# sdcard_ram.net
KiCad netlist of a schematic drawn in Altium Designer
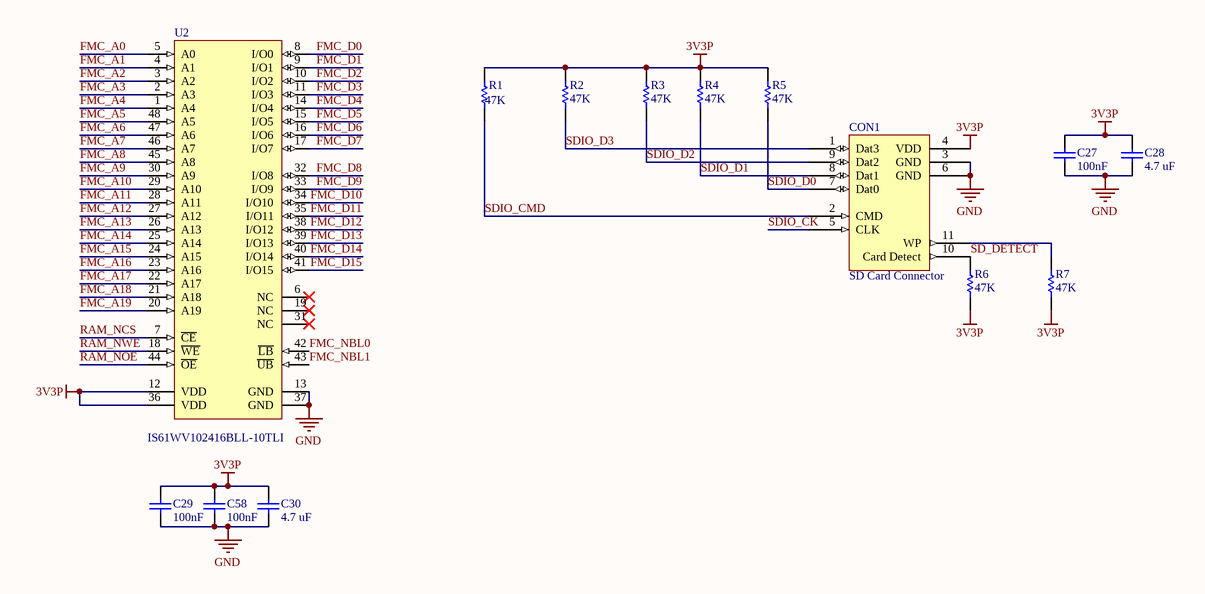
[diagram p0: sdcard_ram.SchDoc]

(export (version "E")
  (design (tool "Eeschema 10.0.6"))
  (components
    (comp (ref "C27")
      (value "100nF")
      (footprint "C0805")
      (description "Capacitor")
      (fields (field (name "PUBLISHER") "Altium Limited"))
      (libsource (lib "Miscellaneous Devices") (part "Cap"))
    )
    (comp (ref "C28")
      (value "4.7 uF")
      (footprint "C0805")
      (description "Capacitor")
      (fields (field (name "PUBLISHER") "Altium Limited"))
      (libsource (lib "Miscellaneous Devices") (part "Cap"))
    )
    (comp (ref "C29")
      (value "100nF")
      (footprint "C0805")
      (description "Capacitor")
      (fields (field (name "PUBLISHER") "Altium Limited"))
      (libsource (lib "Miscellaneous Devices") (part "Cap"))
    )
    (comp (ref "C30")
      (value "4.7 uF")
      (footprint "C0805")
      (description "Capacitor")
      (fields (field (name "PUBLISHER") "Altium Limited"))
      (libsource (lib "Miscellaneous Devices") (part "Cap"))
    )
    (comp (ref "C58")
      (value "100nF")
      (footprint "C0805")
      (description "Capacitor")
      (fields (field (name "PUBLISHER") "Altium Limited"))
      (libsource (lib "Miscellaneous Devices") (part "Cap"))
    )
    (comp (ref "CON1")
      (value "SD Card Connector")
      (footprint "SD_card_fp")
      (description "3M™ Card Connector SD™")
      (libsource (lib "GameMan") (part "SD Card Connector"))
    )
    (comp (ref "R1")
      (value "47K")
      (footprint "6-0805_M")
      (description "Resistor")
      (fields (field (name "PUBLISHER") "Altium Limited"))
      (libsource (lib "Miscellaneous Devices") (part "Res1"))
    )
    (comp (ref "R2")
      (value "47K")
      (footprint "6-0805_M")
      (description "Resistor")
      (fields (field (name "PUBLISHER") "Altium Limited"))
      (libsource (lib "Miscellaneous Devices") (part "Res1"))
    )
    (comp (ref "R3")
      (value "47K")
      (footprint "6-0805_M")
      (description "Resistor")
      (fields (field (name "PUBLISHER") "Altium Limited"))
      (libsource (lib "Miscellaneous Devices") (part "Res1"))
    )
    (comp (ref "R4")
      (value "47K")
      (footprint "6-0805_M")
      (description "Resistor")
      (fields (field (name "PUBLISHER") "Altium Limited"))
      (libsource (lib "Miscellaneous Devices") (part "Res1"))
    )
    (comp (ref "R5")
      (value "47K")
      (footprint "6-0805_M")
      (description "Resistor")
      (fields (field (name "PUBLISHER") "Altium Limited"))
      (libsource (lib "Miscellaneous Devices") (part "Res1"))
    )
    (comp (ref "R6")
      (value "47K")
      (footprint "6-0805_M")
      (description "Resistor")
      (fields (field (name "PUBLISHER") "Altium Limited"))
      (libsource (lib "Miscellaneous Devices") (part "Res1"))
    )
    (comp (ref "R7")
      (value "47K")
      (footprint "6-0805_M")
      (description "Resistor")
      (fields (field (name "PUBLISHER") "Altium Limited"))
      (libsource (lib "Miscellaneous Devices") (part "Res1"))
    )
    (comp (ref "U2")
      (value "IS61WV102416BLL-10TLI")
      (footprint "ISSI-TSOP-1-48-12000X20000DE_N")
      (fields (field (name "MANUFACTURER") "Integrated Silicon Solution Inc (ISSI)"))
      (libsource (lib "ISSI SRAM Asynchronous SRAM High Speed Low Power") (part "IS61WV102416BLL-10TLI"))
    )
  )
  (nets
    (net (code "1") (name "/FMC_A0") (class "Default")
      (node (ref "U2") (pin "5") (pinfunction "A0_5") (pintype "input"))
    )
    (net (code "2") (name "/FMC_A1") (class "Default")
      (node (ref "U2") (pin "4") (pinfunction "A1_4") (pintype "input"))
    )
    (net (code "3") (name "/FMC_A2") (class "Default")
      (node (ref "U2") (pin "3") (pinfunction "A2_3") (pintype "input"))
    )
    (net (code "4") (name "/FMC_A3") (class "Default")
      (node (ref "U2") (pin "2") (pinfunction "A3_2") (pintype "input"))
    )
    (net (code "5") (name "/FMC_A4") (class "Default")
      (node (ref "U2") (pin "1") (pinfunction "A4_1") (pintype "input"))
    )
    (net (code "6") (name "/FMC_A5") (class "Default")
      (node (ref "U2") (pin "48") (pinfunction "A5_48") (pintype "input"))
    )
    (net (code "7") (name "/FMC_A6") (class "Default")
      (node (ref "U2") (pin "47") (pinfunction "A6_47") (pintype "input"))
    )
    (net (code "8") (name "/FMC_A7") (class "Default")
      (node (ref "U2") (pin "46") (pinfunction "A7_46") (pintype "input"))
    )
    (net (code "9") (name "/FMC_A8") (class "Default")
      (node (ref "U2") (pin "45") (pinfunction "A8_45") (pintype "input"))
    )
    (net (code "10") (name "/FMC_A9") (class "Default")
      (node (ref "U2") (pin "30") (pinfunction "A9_30") (pintype "input"))
    )
    (net (code "11") (name "/FMC_A10") (class "Default")
      (node (ref "U2") (pin "29") (pinfunction "A10_29") (pintype "input"))
    )
    (net (code "12") (name "/FMC_A11") (class "Default")
      (node (ref "U2") (pin "28") (pinfunction "A11_28") (pintype "input"))
    )
    (net (code "13") (name "/FMC_A12") (class "Default")
      (node (ref "U2") (pin "27") (pinfunction "A12_27") (pintype "input"))
    )
    (net (code "14") (name "/FMC_A13") (class "Default")
      (node (ref "U2") (pin "26") (pinfunction "A13_26") (pintype "input"))
    )
    (net (code "15") (name "/FMC_A14") (class "Default")
      (node (ref "U2") (pin "25") (pinfunction "A14_25") (pintype "input"))
    )
    (net (code "16") (name "/FMC_A15") (class "Default")
      (node (ref "U2") (pin "24") (pinfunction "A15_24") (pintype "input"))
    )
    (net (code "17") (name "/FMC_A16") (class "Default")
      (node (ref "U2") (pin "23") (pinfunction "A16_23") (pintype "input"))
    )
    (net (code "18") (name "/FMC_A17") (class "Default")
      (node (ref "U2") (pin "22") (pinfunction "A17_22") (pintype "input"))
    )
    (net (code "19") (name "/FMC_A18") (class "Default")
      (node (ref "U2") (pin "21") (pinfunction "A18_21") (pintype "input"))
    )
    (net (code "20") (name "/FMC_A19") (class "Default")
      (node (ref "U2") (pin "20") (pinfunction "A19_20") (pintype "input"))
    )
    (net (code "21") (name "/FMC_D0") (class "Default")
      (node (ref "U2") (pin "8") (pinfunction "I/O0_8") (pintype "bidirectional"))
    )
    (net (code "22") (name "/FMC_D1") (class "Default")
      (node (ref "U2") (pin "9") (pinfunction "I/O1_9") (pintype "bidirectional"))
    )
    (net (code "23") (name "/FMC_D2") (class "Default")
      (node (ref "U2") (pin "10") (pinfunction "I/O2_10") (pintype "bidirectional"))
    )
    (net (code "24") (name "/FMC_D3") (class "Default")
      (node (ref "U2") (pin "11") (pinfunction "I/O3_11") (pintype "bidirectional"))
    )
    (net (code "25") (name "/FMC_D4") (class "Default")
      (node (ref "U2") (pin "14") (pinfunction "I/O4_14") (pintype "bidirectional"))
    )
    (net (code "26") (name "/FMC_D5") (class "Default")
      (node (ref "U2") (pin "15") (pinfunction "I/O5_15") (pintype "bidirectional"))
    )
    (net (code "27") (name "/FMC_D6") (class "Default")
      (node (ref "U2") (pin "16") (pinfunction "I/O6_16") (pintype "bidirectional"))
    )
    (net (code "28") (name "/FMC_D7") (class "Default")
      (node (ref "U2") (pin "17") (pinfunction "I/O7_17") (pintype "bidirectional"))
    )
    (net (code "29") (name "/FMC_D8") (class "Default")
      (node (ref "U2") (pin "32") (pinfunction "I/O8_32") (pintype "bidirectional"))
    )
    (net (code "30") (name "/FMC_D9") (class "Default")
      (node (ref "U2") (pin "33") (pinfunction "I/O9_33") (pintype "bidirectional"))
    )
    (net (code "31") (name "/FMC_D10") (class "Default")
      (node (ref "U2") (pin "34") (pinfunction "I/O10_34") (pintype "bidirectional"))
    )
    (net (code "32") (name "/FMC_D11") (class "Default")
      (node (ref "U2") (pin "35") (pinfunction "I/O11_35") (pintype "bidirectional"))
    )
    (net (code "33") (name "/FMC_D12") (class "Default")
      (node (ref "U2") (pin "38") (pinfunction "I/O12_38") (pintype "bidirectional"))
    )
    (net (code "34") (name "/FMC_D13") (class "Default")
      (node (ref "U2") (pin "39") (pinfunction "I/O13_39") (pintype "bidirectional"))
    )
    (net (code "35") (name "/FMC_D14") (class "Default")
      (node (ref "U2") (pin "40") (pinfunction "I/O14_40") (pintype "bidirectional"))
    )
    (net (code "36") (name "/FMC_D15") (class "Default")
      (node (ref "U2") (pin "41") (pinfunction "I/O15_41") (pintype "bidirectional"))
    )
    (net (code "37") (name "/FMC_NBL0") (class "Default")
      (node (ref "U2") (pin "42") (pinfunction "~{LB}_42") (pintype "input"))
    )
    (net (code "38") (name "/FMC_NBL1") (class "Default")
      (node (ref "U2") (pin "43") (pinfunction "~{UB}_43") (pintype "input"))
    )
    (net (code "39") (name "/RAM_NCS") (class "Default")
      (node (ref "U2") (pin "7") (pinfunction "~{CE}_7") (pintype "input"))
    )
    (net (code "40") (name "/RAM_NOE") (class "Default")
      (node (ref "U2") (pin "44") (pinfunction "~{OE}_44") (pintype "input"))
    )
    (net (code "41") (name "/RAM_NWE") (class "Default")
      (node (ref "U2") (pin "18") (pinfunction "~{WE}_18") (pintype "input"))
    )
    (net (code "42") (name "/SDIO_CK") (class "Default")
      (node (ref "CON1") (pin "5") (pinfunction "CLK_5") (pintype "input"))
    )
    (net (code "43") (name "/SDIO_CMD") (class "Default")
      (node (ref "CON1") (pin "2") (pinfunction "CMD_2") (pintype "input"))
      (node (ref "R1") (pin "1") (pinfunction "1_1") (pintype "passive"))
    )
    (net (code "44") (name "/SDIO_D0") (class "Default")
      (node (ref "CON1") (pin "7") (pinfunction "Dat0_7") (pintype "bidirectional"))
      (node (ref "R5") (pin "1") (pinfunction "1_1") (pintype "passive"))
    )
    (net (code "45") (name "/SDIO_D1") (class "Default")
      (node (ref "CON1") (pin "8") (pinfunction "Dat1_8") (pintype "bidirectional"))
      (node (ref "R4") (pin "1") (pinfunction "1_1") (pintype "passive"))
    )
    (net (code "46") (name "/SDIO_D2") (class "Default")
      (node (ref "CON1") (pin "9") (pinfunction "Dat2_9") (pintype "bidirectional"))
      (node (ref "R3") (pin "1") (pinfunction "1_1") (pintype "passive"))
    )
    (net (code "47") (name "/SDIO_D3") (class "Default")
      (node (ref "CON1") (pin "1") (pinfunction "Dat3_1") (pintype "bidirectional"))
      (node (ref "R2") (pin "1") (pinfunction "1_1") (pintype "passive"))
    )
    (net (code "48") (name "/SD_DETECT") (class "Default")
      (node (ref "CON1") (pin "10") (pinfunction "Card_Detect_10") (pintype "output"))
      (node (ref "R6") (pin "2") (pinfunction "2_2") (pintype "passive"))
    )
    (net (code "49") (name "3V3P") (class "Default")
      (node (ref "C27") (pin "2") (pinfunction "2_2") (pintype "passive"))
      (node (ref "C28") (pin "2") (pinfunction "2_2") (pintype "passive"))
      (node (ref "C29") (pin "2") (pinfunction "2_2") (pintype "passive"))
      (node (ref "C30") (pin "2") (pinfunction "2_2") (pintype "passive"))
      (node (ref "C58") (pin "2") (pinfunction "2_2") (pintype "passive"))
      (node (ref "CON1") (pin "4") (pinfunction "VDD_4") (pintype "power_in"))
      (node (ref "R1") (pin "2") (pinfunction "2_2") (pintype "passive"))
      (node (ref "R2") (pin "2") (pinfunction "2_2") (pintype "passive"))
      (node (ref "R3") (pin "2") (pinfunction "2_2") (pintype "passive"))
      (node (ref "R4") (pin "2") (pinfunction "2_2") (pintype "passive"))
      (node (ref "R5") (pin "2") (pinfunction "2_2") (pintype "passive"))
      (node (ref "R6") (pin "1") (pinfunction "1_1") (pintype "passive"))
      (node (ref "R7") (pin "1") (pinfunction "1_1") (pintype "passive"))
      (node (ref "U2") (pin "12") (pinfunction "VDD_12") (pintype "power_in"))
      (node (ref "U2") (pin "36") (pinfunction "VDD_36") (pintype "power_in"))
    )
    (net (code "50") (name "GND") (class "Default")
      (node (ref "C27") (pin "1") (pinfunction "1_1") (pintype "passive"))
      (node (ref "C28") (pin "1") (pinfunction "1_1") (pintype "passive"))
      (node (ref "C29") (pin "1") (pinfunction "1_1") (pintype "passive"))
      (node (ref "C30") (pin "1") (pinfunction "1_1") (pintype "passive"))
      (node (ref "C58") (pin "1") (pinfunction "1_1") (pintype "passive"))
      (node (ref "CON1") (pin "3") (pinfunction "GND_3") (pintype "power_in"))
      (node (ref "CON1") (pin "6") (pinfunction "GND_6") (pintype "power_in"))
      (node (ref "U2") (pin "13") (pinfunction "GND_13") (pintype "power_in"))
      (node (ref "U2") (pin "37") (pinfunction "GND_37") (pintype "power_in"))
    )
    (net (code "51") (name "Net-(CON1-WP)") (class "Default")
      (node (ref "CON1") (pin "11") (pinfunction "WP_11") (pintype "output"))
      (node (ref "R7") (pin "2") (pinfunction "2_2") (pintype "passive"))
    )
    (net (code "52") (name "unconnected-(U2-NC-Pad6)") (class "Default")
      (node (ref "U2") (pin "6") (pinfunction "NC_6") (pintype "passive+no_connect"))
    )
    (net (code "53") (name "unconnected-(U2-NC-Pad19)") (class "Default")
      (node (ref "U2") (pin "19") (pinfunction "NC_19") (pintype "passive+no_connect"))
    )
    (net (code "54") (name "unconnected-(U2-NC-Pad31)") (class "Default")
      (node (ref "U2") (pin "31") (pinfunction "NC_31") (pintype "passive+no_connect"))
    )
  )
)
